# ADP5090.net
KiCad netlist of a schematic drawn in EAGLE
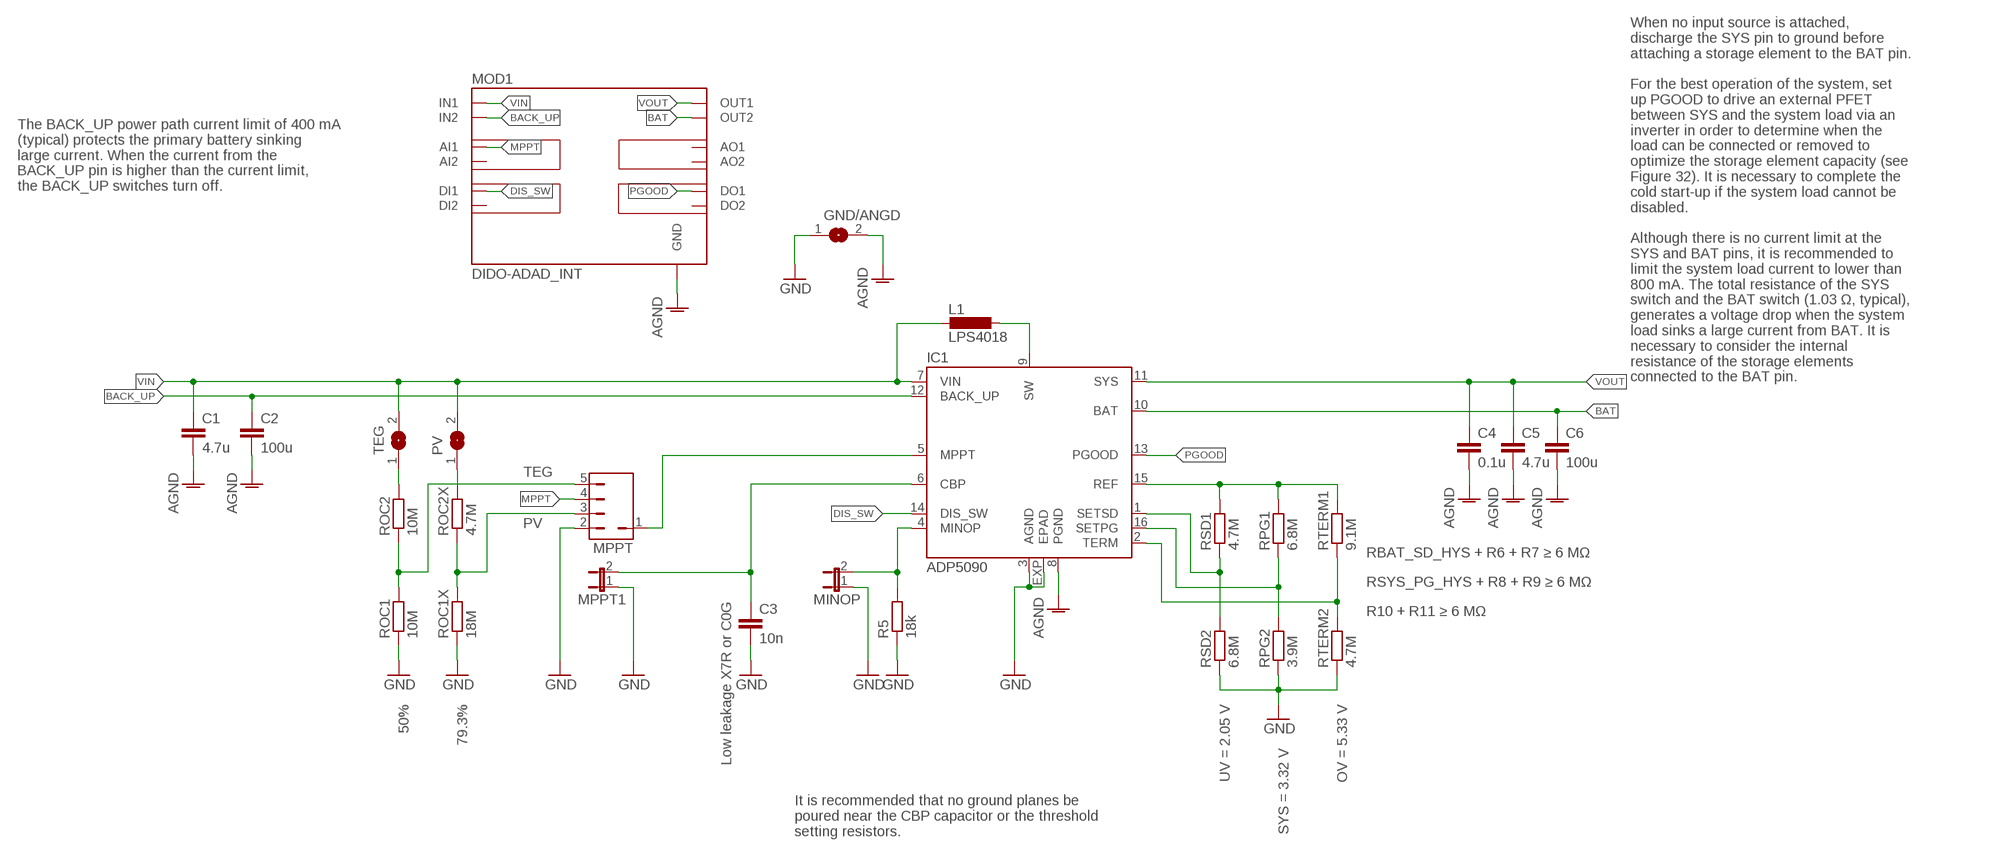
[diagram p0: schematic, sheet 1]

(export (version "E")
  (design (tool "Eeschema 10.0.6"))
  (components
    (comp (ref "C1")
      (value "4.7u")
      (footprint "eagle-import:C0805")
      (libsource (lib "eagle-import") (part "C-EUC0805"))
    )
    (comp (ref "C2")
      (value "100u")
      (footprint "eagle-import:C0805")
      (libsource (lib "eagle-import") (part "C-EUC0805"))
    )
    (comp (ref "C3")
      (value "10n")
      (footprint "eagle-import:C0805")
      (libsource (lib "eagle-import") (part "C-EUC0805"))
    )
    (comp (ref "C4")
      (value "0.1u")
      (footprint "eagle-import:C0805")
      (libsource (lib "eagle-import") (part "C-EUC0805"))
    )
    (comp (ref "C5")
      (value "4.7u")
      (footprint "eagle-import:C0805")
      (libsource (lib "eagle-import") (part "C-EUC0805"))
    )
    (comp (ref "C6")
      (value "100u")
      (footprint "eagle-import:C0805")
      (libsource (lib "eagle-import") (part "C-EUC0805"))
    )
    (comp (ref "GND/ANGD")
      (value "SJ")
      (footprint "eagle-import:SJ")
      (libsource (lib "eagle-import") (part "SJ"))
    )
    (comp (ref "IC1")
      (value "ADP5090")
      (footprint "eagle-import:LFCSP16_WQ_CP-16-33")
      (libsource (lib "eagle-import") (part "ADP5090"))
    )
    (comp (ref "L1")
      (value "LPS4018")
      (footprint "eagle-import:LPS4018")
      (libsource (lib "eagle-import") (part "LPS4018"))
    )
    (comp (ref "MINOP")
      (value "JP1E")
      (footprint "eagle-import:JP1")
      (libsource (lib "eagle-import") (part "JP1E"))
    )
    (comp (ref "MOD1")
      (value "DIDO-ADAD_INT")
      (footprint "eagle-import:DIDO-ADAD")
      (libsource (lib "eagle-import") (part "DIDO-ADAD_INT"))
    )
    (comp (ref "MPPT")
      (value "JP3Q")
      (footprint "eagle-import:JP1-4")
      (libsource (lib "eagle-import") (part "JP3Q"))
    )
    (comp (ref "MPPT1")
      (value "JP1E")
      (footprint "eagle-import:JP1")
      (libsource (lib "eagle-import") (part "JP1E"))
    )
    (comp (ref "PV") (value "SJ") (footprint "eagle-import:SJ") (libsource (lib "eagle-import") (part "SJ")))
    (comp (ref "R5")
      (value "18k")
      (footprint "eagle-import:R0805")
      (libsource (lib "eagle-import") (part "R-EU_R0805"))
    )
    (comp (ref "ROC1")
      (value "10M")
      (footprint "eagle-import:R0805")
      (libsource (lib "eagle-import") (part "R-EU_R0805"))
    )
    (comp (ref "ROC1X")
      (value "18M")
      (footprint "eagle-import:R0805")
      (libsource (lib "eagle-import") (part "R-EU_R0805"))
    )
    (comp (ref "ROC2")
      (value "10M")
      (footprint "eagle-import:R0805")
      (libsource (lib "eagle-import") (part "R-EU_R0805"))
    )
    (comp (ref "ROC2X")
      (value "4.7M")
      (footprint "eagle-import:R0805")
      (libsource (lib "eagle-import") (part "R-EU_R0805"))
    )
    (comp (ref "RPG1")
      (value "6.8M")
      (footprint "eagle-import:R0805")
      (libsource (lib "eagle-import") (part "R-EU_R0805"))
    )
    (comp (ref "RPG2")
      (value "3.9M")
      (footprint "eagle-import:R0805")
      (libsource (lib "eagle-import") (part "R-EU_R0805"))
    )
    (comp (ref "RSD1")
      (value "4.7M")
      (footprint "eagle-import:R0805")
      (libsource (lib "eagle-import") (part "R-EU_R0805"))
    )
    (comp (ref "RSD2")
      (value "6.8M")
      (footprint "eagle-import:R0805")
      (libsource (lib "eagle-import") (part "R-EU_R0805"))
    )
    (comp (ref "RTERM1")
      (value "9.1M")
      (footprint "eagle-import:R0805")
      (libsource (lib "eagle-import") (part "R-EU_R0805"))
    )
    (comp (ref "RTERM2")
      (value "4.7M")
      (footprint "eagle-import:R0805")
      (libsource (lib "eagle-import") (part "R-EU_R0805"))
    )
    (comp (ref "TEG") (value "SJ") (footprint "eagle-import:SJ") (libsource (lib "eagle-import") (part "SJ")))
  )
  (nets
    (net (code "1") (name "AGND") (class "Default")
      (node (ref "C1") (pin "2") (pinfunction "2_2") (pintype "passive"))
      (node (ref "C2") (pin "2") (pinfunction "2_2") (pintype "passive"))
      (node (ref "C4") (pin "2") (pinfunction "2_2") (pintype "passive"))
      (node (ref "C5") (pin "2") (pinfunction "2_2") (pintype "passive"))
      (node (ref "C6") (pin "2") (pinfunction "2_2") (pintype "passive"))
      (node (ref "GND/ANGD") (pin "2") (pinfunction "2_2") (pintype "passive"))
      (node (ref "IC1") (pin "8") (pinfunction "PGND_8") (pintype "power_in"))
      (node (ref "MOD1") (pin "GND1") (pinfunction "GND_GND1") (pintype "power_in"))
      (node (ref "MOD1") (pin "GND2") (pinfunction "GND_GND2") (pintype "power_in"))
      (node (ref "MOD1") (pin "GND3") (pinfunction "GND_GND3") (pintype "power_in"))
      (node (ref "MOD1") (pin "GND4") (pinfunction "GND_GND4") (pintype "power_in"))
    )
    (net (code "2") (name "BACK_UP") (class "Default")
      (node (ref "C2") (pin "1") (pinfunction "1_1") (pintype "passive"))
      (node (ref "IC1") (pin "12") (pinfunction "BACK_UP_12") (pintype "power_in"))
      (node (ref "MOD1") (pin "IN2_1") (pinfunction "IN2_IN2_1") (pintype "output"))
      (node (ref "MOD1") (pin "IN2_2") (pinfunction "IN2_IN2_2") (pintype "output"))
      (node (ref "MOD1") (pin "IN2_3") (pinfunction "IN2_IN2_3") (pintype "output"))
      (node (ref "MOD1") (pin "IN2_4") (pinfunction "IN2_IN2_4") (pintype "output"))
    )
    (net (code "3") (name "BAT") (class "Default")
      (node (ref "C6") (pin "1") (pinfunction "1_1") (pintype "passive"))
      (node (ref "IC1") (pin "10") (pinfunction "BAT_10") (pintype "output"))
      (node (ref "MOD1") (pin "OUT2_1") (pinfunction "OUT2_OUT2_1") (pintype "input"))
      (node (ref "MOD1") (pin "OUT2_2") (pinfunction "OUT2_OUT2_2") (pintype "input"))
      (node (ref "MOD1") (pin "OUT2_3") (pinfunction "OUT2_OUT2_3") (pintype "input"))
      (node (ref "MOD1") (pin "OUT2_4") (pinfunction "OUT2_OUT2_4") (pintype "input"))
    )
    (net (code "4") (name "DIS_SW") (class "Default")
      (node (ref "IC1") (pin "14") (pinfunction "DIS_SW_14") (pintype "passive"))
      (node (ref "MOD1") (pin "DI1") (pinfunction "DI1_DI1") (pintype "output"))
    )
    (net (code "5") (name "GND") (class "Default")
      (node (ref "C3") (pin "2") (pinfunction "2_2") (pintype "passive"))
      (node (ref "GND/ANGD") (pin "1") (pinfunction "1_1") (pintype "passive"))
      (node (ref "IC1") (pin "3") (pinfunction "AGND_3") (pintype "power_in"))
      (node (ref "IC1") (pin "EXP") (pinfunction "EPAD_EXP") (pintype "power_in"))
      (node (ref "MINOP") (pin "1") (pinfunction "1_1") (pintype "passive"))
      (node (ref "MPPT") (pin "2") (pinfunction "2_2") (pintype "passive"))
      (node (ref "MPPT1") (pin "1") (pinfunction "1_1") (pintype "passive"))
      (node (ref "R5") (pin "1") (pinfunction "1_1") (pintype "passive"))
      (node (ref "ROC1") (pin "1") (pinfunction "1_1") (pintype "passive"))
      (node (ref "ROC1X") (pin "1") (pinfunction "1_1") (pintype "passive"))
      (node (ref "RPG2") (pin "1") (pinfunction "1_1") (pintype "passive"))
      (node (ref "RSD2") (pin "1") (pinfunction "1_1") (pintype "passive"))
      (node (ref "RTERM2") (pin "1") (pinfunction "1_1") (pintype "passive"))
    )
    (net (code "6") (name "MPPT") (class "Default")
      (node (ref "MOD1") (pin "AI1") (pinfunction "AI1_AI1") (pintype "output"))
      (node (ref "MPPT") (pin "4") (pinfunction "4_4") (pintype "passive"))
    )
    (net (code "7") (name "Net-(IC1-CBP)") (class "Default")
      (node (ref "C3") (pin "1") (pinfunction "1_1") (pintype "passive"))
      (node (ref "IC1") (pin "6") (pinfunction "CBP_6") (pintype "passive"))
      (node (ref "MPPT1") (pin "2") (pinfunction "2_2") (pintype "passive"))
    )
    (net (code "8") (name "Net-(IC1-MINOP)") (class "Default")
      (node (ref "IC1") (pin "4") (pinfunction "MINOP_4") (pintype "passive"))
      (node (ref "MINOP") (pin "2") (pinfunction "2_2") (pintype "passive"))
      (node (ref "R5") (pin "2") (pinfunction "2_2") (pintype "passive"))
    )
    (net (code "9") (name "Net-(IC1-MPPT)") (class "Default")
      (node (ref "IC1") (pin "5") (pinfunction "MPPT_5") (pintype "passive"))
      (node (ref "MPPT") (pin "1") (pinfunction "1_1") (pintype "passive"))
    )
    (net (code "10") (name "Net-(IC1-REF)") (class "Default")
      (node (ref "IC1") (pin "15") (pinfunction "REF_15") (pintype "output"))
      (node (ref "RPG1") (pin "2") (pinfunction "2_2") (pintype "passive"))
      (node (ref "RSD1") (pin "2") (pinfunction "2_2") (pintype "passive"))
      (node (ref "RTERM1") (pin "2") (pinfunction "2_2") (pintype "passive"))
    )
    (net (code "11") (name "Net-(IC1-SETPG)") (class "Default")
      (node (ref "IC1") (pin "16") (pinfunction "SETPG_16") (pintype "passive"))
      (node (ref "RPG1") (pin "1") (pinfunction "1_1") (pintype "passive"))
      (node (ref "RPG2") (pin "2") (pinfunction "2_2") (pintype "passive"))
    )
    (net (code "12") (name "Net-(IC1-SETSD)") (class "Default")
      (node (ref "IC1") (pin "1") (pinfunction "SETSD_1") (pintype "passive"))
      (node (ref "RSD1") (pin "1") (pinfunction "1_1") (pintype "passive"))
      (node (ref "RSD2") (pin "2") (pinfunction "2_2") (pintype "passive"))
    )
    (net (code "13") (name "Net-(IC1-SW)") (class "Default")
      (node (ref "IC1") (pin "9") (pinfunction "SW_9") (pintype "passive"))
      (node (ref "L1") (pin "2") (pinfunction "2_2") (pintype "passive"))
    )
    (net (code "14") (name "Net-(IC1-TERM)") (class "Default")
      (node (ref "IC1") (pin "2") (pinfunction "TERM_2") (pintype "passive"))
      (node (ref "RTERM1") (pin "1") (pinfunction "1_1") (pintype "passive"))
      (node (ref "RTERM2") (pin "2") (pinfunction "2_2") (pintype "passive"))
    )
    (net (code "15") (name "Net-(MPPT-Pad3)") (class "Default")
      (node (ref "MPPT") (pin "3") (pinfunction "3_3") (pintype "passive"))
      (node (ref "ROC1X") (pin "2") (pinfunction "2_2") (pintype "passive"))
      (node (ref "ROC2X") (pin "1") (pinfunction "1_1") (pintype "passive"))
    )
    (net (code "16") (name "Net-(MPPT-Pad5)") (class "Default")
      (node (ref "MPPT") (pin "5") (pinfunction "5_5") (pintype "passive"))
      (node (ref "ROC1") (pin "2") (pinfunction "2_2") (pintype "passive"))
      (node (ref "ROC2") (pin "1") (pinfunction "1_1") (pintype "passive"))
    )
    (net (code "17") (name "Net-(PV-Pad1)") (class "Default")
      (node (ref "PV") (pin "1") (pinfunction "1_1") (pintype "passive"))
      (node (ref "ROC2X") (pin "2") (pinfunction "2_2") (pintype "passive"))
    )
    (net (code "18") (name "Net-(ROC2-Pad2)") (class "Default")
      (node (ref "ROC2") (pin "2") (pinfunction "2_2") (pintype "passive"))
      (node (ref "TEG") (pin "1") (pinfunction "1_1") (pintype "passive"))
    )
    (net (code "19") (name "PGOOD") (class "Default")
      (node (ref "IC1") (pin "13") (pinfunction "PGOOD_13") (pintype "output"))
      (node (ref "MOD1") (pin "DO1") (pinfunction "DO1_DO1") (pintype "input"))
    )
    (net (code "20") (name "VIN") (class "Default")
      (node (ref "C1") (pin "1") (pinfunction "1_1") (pintype "passive"))
      (node (ref "IC1") (pin "7") (pinfunction "VIN_7") (pintype "power_in"))
      (node (ref "L1") (pin "1") (pinfunction "1_1") (pintype "passive"))
      (node (ref "MOD1") (pin "IN1_1") (pinfunction "IN1_IN1_1") (pintype "output"))
      (node (ref "MOD1") (pin "IN1_2") (pinfunction "IN1_IN1_2") (pintype "output"))
      (node (ref "MOD1") (pin "IN1_3") (pinfunction "IN1_IN1_3") (pintype "output"))
      (node (ref "MOD1") (pin "IN1_4") (pinfunction "IN1_IN1_4") (pintype "output"))
      (node (ref "PV") (pin "2") (pinfunction "2_2") (pintype "passive"))
      (node (ref "TEG") (pin "2") (pinfunction "2_2") (pintype "passive"))
    )
    (net (code "21") (name "VOUT") (class "Default")
      (node (ref "C4") (pin "1") (pinfunction "1_1") (pintype "passive"))
      (node (ref "C5") (pin "1") (pinfunction "1_1") (pintype "passive"))
      (node (ref "IC1") (pin "11") (pinfunction "SYS_11") (pintype "output"))
      (node (ref "MOD1") (pin "OUT1_1") (pinfunction "OUT1_OUT1_1") (pintype "input"))
      (node (ref "MOD1") (pin "OUT1_2") (pinfunction "OUT1_OUT1_2") (pintype "input"))
      (node (ref "MOD1") (pin "OUT1_3") (pinfunction "OUT1_OUT1_3") (pintype "input"))
      (node (ref "MOD1") (pin "OUT1_4") (pinfunction "OUT1_OUT1_4") (pintype "input"))
    )
    (net (code "22") (name "unconnected-(MOD1-PadAI2)") (class "Default")
      (node (ref "MOD1") (pin "AI2") (pinfunction "AI2_AI2") (pintype "output"))
    )
    (net (code "23") (name "unconnected-(MOD1-PadAO1)") (class "Default")
      (node (ref "MOD1") (pin "AO1") (pinfunction "AO1_AO1") (pintype "input"))
    )
    (net (code "24") (name "unconnected-(MOD1-PadAO2)") (class "Default")
      (node (ref "MOD1") (pin "AO2") (pinfunction "AO2_AO2") (pintype "input"))
    )
    (net (code "25") (name "unconnected-(MOD1-PadDI2)") (class "Default")
      (node (ref "MOD1") (pin "DI2") (pinfunction "DI2_DI2") (pintype "output"))
    )
    (net (code "26") (name "unconnected-(MOD1-PadDO2)") (class "Default")
      (node (ref "MOD1") (pin "DO2") (pinfunction "DO2_DO2") (pintype "input"))
    )
  )
)
